# Xplained_RFM98W.net
KiCad netlist of a schematic drawn in EAGLE
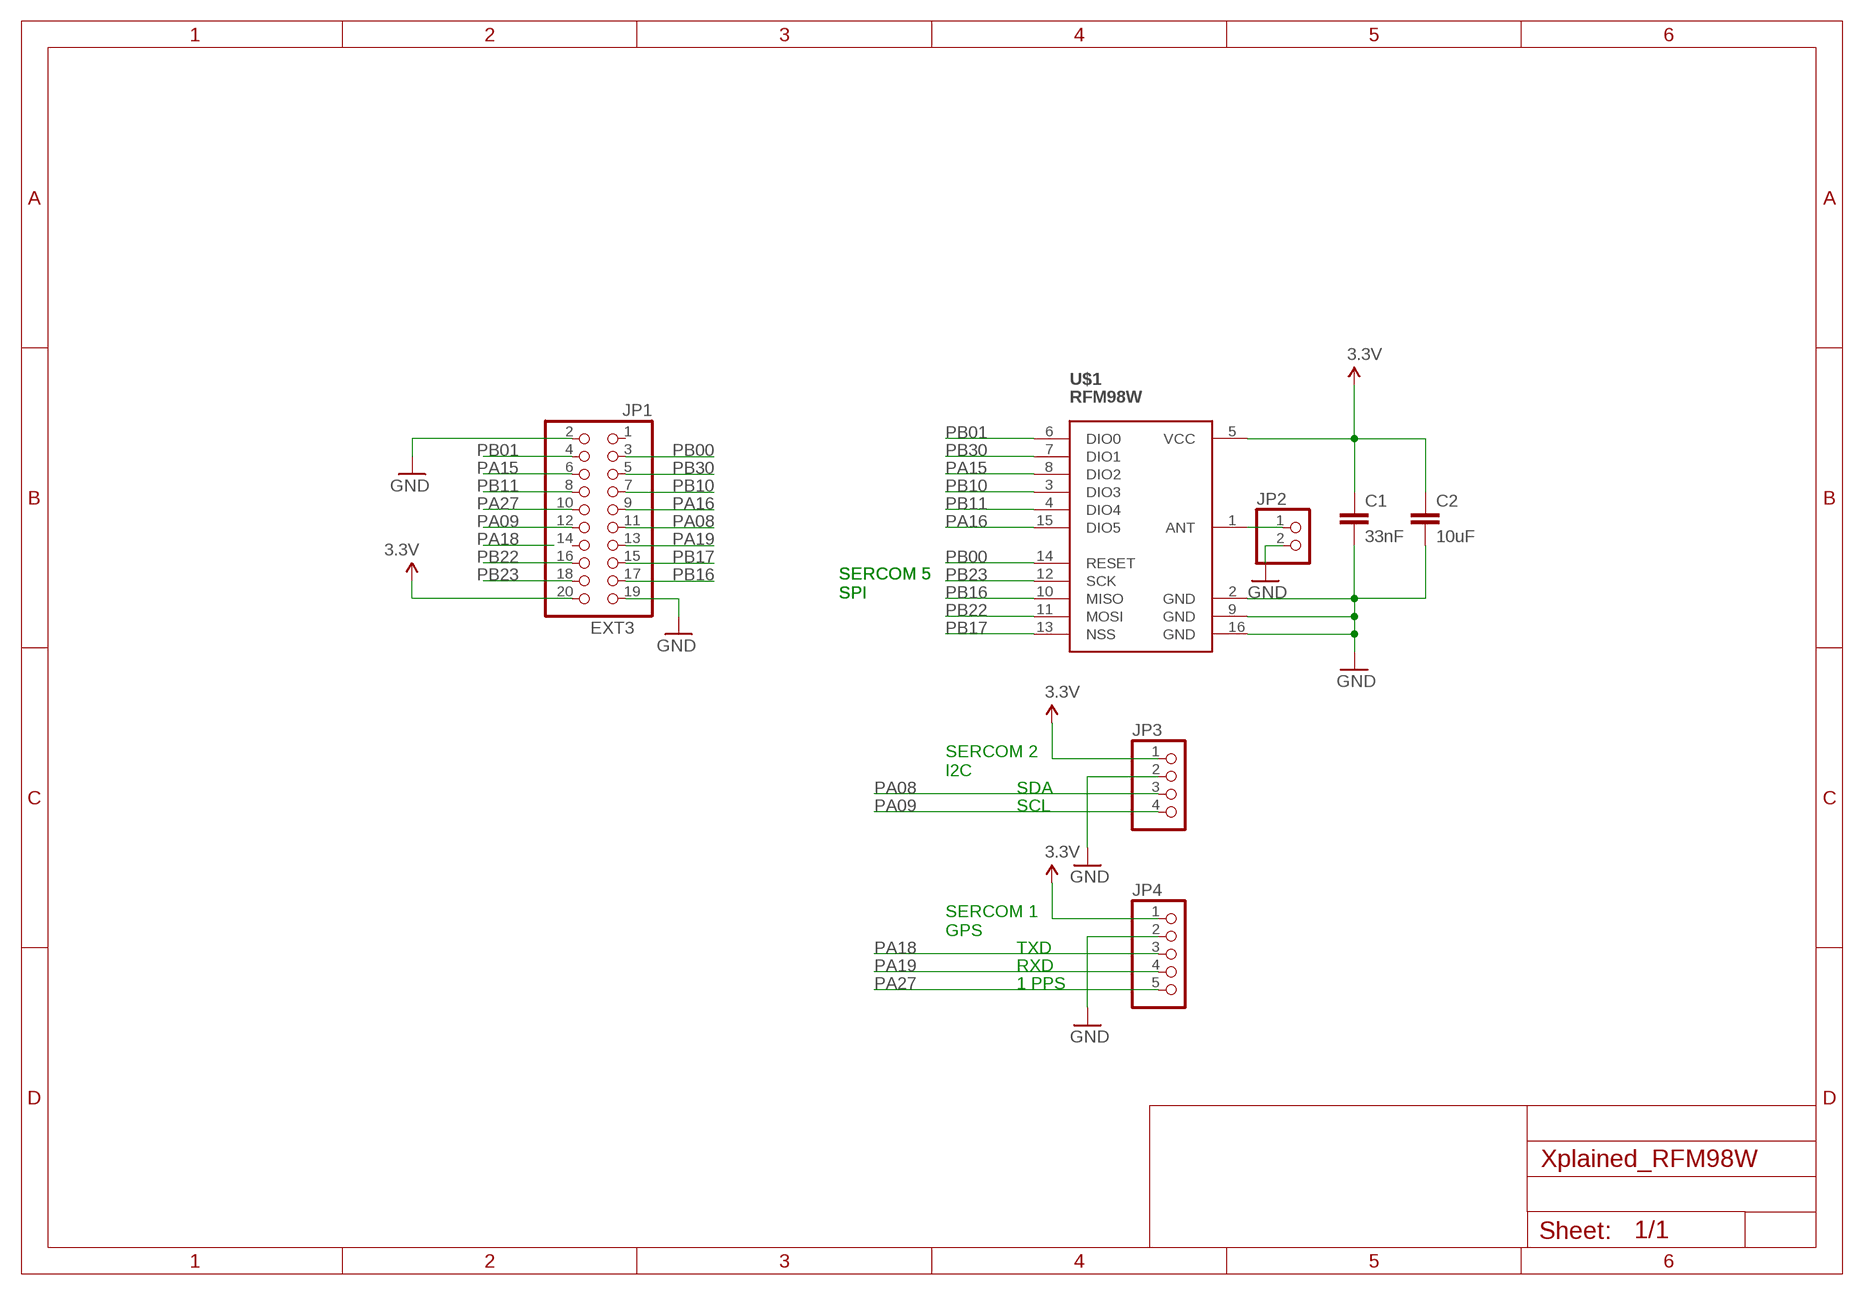
[diagram p0: schematic, sheet 1]

(export (version "E")
  (design (tool "Eeschema 10.0.6"))
  (components
    (comp (ref "C1")
      (value "33nF")
      (footprint "eagle-import:0603-CAP")
      (libsource (lib "eagle-import") (part "CAP0603-CAP"))
    )
    (comp (ref "C2")
      (value "10uF")
      (footprint "eagle-import:0603-CAP")
      (libsource (lib "eagle-import") (part "CAP0603-CAP"))
    )
    (comp (ref "JP1")
      (value "EXT3")
      (footprint "eagle-import:2X10_90")
      (libsource (lib "eagle-import") (part "PINHD-2X10/90"))
    )
    (comp (ref "JP2")
      (value "PINHD-1X2")
      (footprint "eagle-import:1X02")
      (libsource (lib "eagle-import") (part "PINHD-1X2"))
    )
    (comp (ref "JP3")
      (value "PINHD-1X4/90")
      (footprint "eagle-import:1X04_90")
      (libsource (lib "eagle-import") (part "PINHD-1X4/90"))
    )
    (comp (ref "JP4")
      (value "PINHD-1X5/90")
      (footprint "eagle-import:1X05_90")
      (libsource (lib "eagle-import") (part "PINHD-1X5/90"))
    )
    (comp (ref "U$1")
      (value "RFM98W")
      (footprint "eagle-import:MODULE_16X16_16PIN")
      (libsource (lib "eagle-import") (part "RFM66W_69HCW_9XW"))
    )
  )
  (nets
    (net (code "1") (name "/PA08") (class "Default")
      (node (ref "JP1") (pin "11") (pinfunction "11_11") (pintype "passive"))
      (node (ref "JP3") (pin "3") (pinfunction "3_3") (pintype "passive"))
    )
    (net (code "2") (name "/PA09") (class "Default")
      (node (ref "JP1") (pin "12") (pinfunction "12_12") (pintype "passive"))
      (node (ref "JP3") (pin "4") (pinfunction "4_4") (pintype "passive"))
    )
    (net (code "3") (name "/PA15") (class "Default")
      (node (ref "JP1") (pin "6") (pinfunction "6_6") (pintype "passive"))
      (node (ref "U$1") (pin "8") (pinfunction "DIO2_8") (pintype "bidirectional"))
    )
    (net (code "4") (name "/PA16") (class "Default")
      (node (ref "JP1") (pin "9") (pinfunction "9_9") (pintype "passive"))
      (node (ref "U$1") (pin "15") (pinfunction "DIO5_15") (pintype "bidirectional"))
    )
    (net (code "5") (name "/PA18") (class "Default")
      (node (ref "JP4") (pin "3") (pinfunction "3_3") (pintype "passive"))
    )
    (net (code "6") (name "/PA19") (class "Default")
      (node (ref "JP1") (pin "13") (pinfunction "13_13") (pintype "passive"))
      (node (ref "JP4") (pin "4") (pinfunction "4_4") (pintype "passive"))
    )
    (net (code "7") (name "/PA27") (class "Default")
      (node (ref "JP1") (pin "10") (pinfunction "10_10") (pintype "passive"))
      (node (ref "JP4") (pin "5") (pinfunction "5_5") (pintype "passive"))
    )
    (net (code "8") (name "/PB00") (class "Default")
      (node (ref "JP1") (pin "3") (pinfunction "3_3") (pintype "passive"))
      (node (ref "U$1") (pin "14") (pinfunction "RESET_14") (pintype "bidirectional"))
    )
    (net (code "9") (name "/PB01") (class "Default")
      (node (ref "JP1") (pin "4") (pinfunction "4_4") (pintype "passive"))
      (node (ref "U$1") (pin "6") (pinfunction "DIO0_6") (pintype "bidirectional"))
    )
    (net (code "10") (name "/PB10") (class "Default")
      (node (ref "JP1") (pin "7") (pinfunction "7_7") (pintype "passive"))
      (node (ref "U$1") (pin "3") (pinfunction "DIO3_3") (pintype "bidirectional"))
    )
    (net (code "11") (name "/PB11") (class "Default")
      (node (ref "JP1") (pin "8") (pinfunction "8_8") (pintype "passive"))
      (node (ref "U$1") (pin "4") (pinfunction "DIO4_4") (pintype "bidirectional"))
    )
    (net (code "12") (name "/PB16") (class "Default")
      (node (ref "JP1") (pin "17") (pinfunction "17_17") (pintype "passive"))
      (node (ref "U$1") (pin "10") (pinfunction "MISO_10") (pintype "bidirectional"))
    )
    (net (code "13") (name "/PB17") (class "Default")
      (node (ref "JP1") (pin "15") (pinfunction "15_15") (pintype "passive"))
      (node (ref "U$1") (pin "13") (pinfunction "NSS_13") (pintype "bidirectional"))
    )
    (net (code "14") (name "/PB22") (class "Default")
      (node (ref "JP1") (pin "16") (pinfunction "16_16") (pintype "passive"))
      (node (ref "U$1") (pin "11") (pinfunction "MOSI_11") (pintype "bidirectional"))
    )
    (net (code "15") (name "/PB23") (class "Default")
      (node (ref "JP1") (pin "18") (pinfunction "18_18") (pintype "passive"))
      (node (ref "U$1") (pin "12") (pinfunction "SCK_12") (pintype "bidirectional"))
    )
    (net (code "16") (name "/PB30") (class "Default")
      (node (ref "JP1") (pin "5") (pinfunction "5_5") (pintype "passive"))
      (node (ref "U$1") (pin "7") (pinfunction "DIO1_7") (pintype "bidirectional"))
    )
    (net (code "17") (name "3.3V") (class "Default")
      (node (ref "C1") (pin "1") (pinfunction "1_1") (pintype "passive"))
      (node (ref "C2") (pin "1") (pinfunction "1_1") (pintype "passive"))
      (node (ref "JP1") (pin "20") (pinfunction "20_20") (pintype "passive"))
      (node (ref "JP3") (pin "1") (pinfunction "1_1") (pintype "passive"))
      (node (ref "JP4") (pin "1") (pinfunction "1_1") (pintype "passive"))
      (node (ref "U$1") (pin "5") (pinfunction "VCC_5") (pintype "bidirectional"))
    )
    (net (code "18") (name "GND") (class "Default")
      (node (ref "C1") (pin "2") (pinfunction "2_2") (pintype "passive"))
      (node (ref "C2") (pin "2") (pinfunction "2_2") (pintype "passive"))
      (node (ref "JP1") (pin "19") (pinfunction "19_19") (pintype "passive"))
      (node (ref "JP1") (pin "2") (pinfunction "2_2") (pintype "passive"))
      (node (ref "JP2") (pin "2") (pinfunction "2_2") (pintype "passive"))
      (node (ref "JP3") (pin "2") (pinfunction "2_2") (pintype "passive"))
      (node (ref "JP4") (pin "2") (pinfunction "2_2") (pintype "passive"))
      (node (ref "U$1") (pin "16") (pinfunction "GND_16") (pintype "bidirectional"))
      (node (ref "U$1") (pin "2") (pinfunction "GND_2") (pintype "bidirectional"))
      (node (ref "U$1") (pin "9") (pinfunction "GND_9") (pintype "bidirectional"))
    )
    (net (code "19") (name "Net-(U$1-ANT)") (class "Default")
      (node (ref "JP2") (pin "1") (pinfunction "1_1") (pintype "passive"))
      (node (ref "U$1") (pin "1") (pinfunction "ANT_1") (pintype "bidirectional"))
    )
    (net (code "20") (name "unconnected-(JP1-Pad1)") (class "Default")
      (node (ref "JP1") (pin "1") (pinfunction "1_1") (pintype "passive"))
    )
    (net (code "21") (name "unconnected-(JP1-Pad14)") (class "Default")
      (node (ref "JP1") (pin "14") (pinfunction "14_14") (pintype "passive"))
    )
  )
)
